# A3000_Backplane.net
KiCad netlist of a schematic drawn in Altium Designer
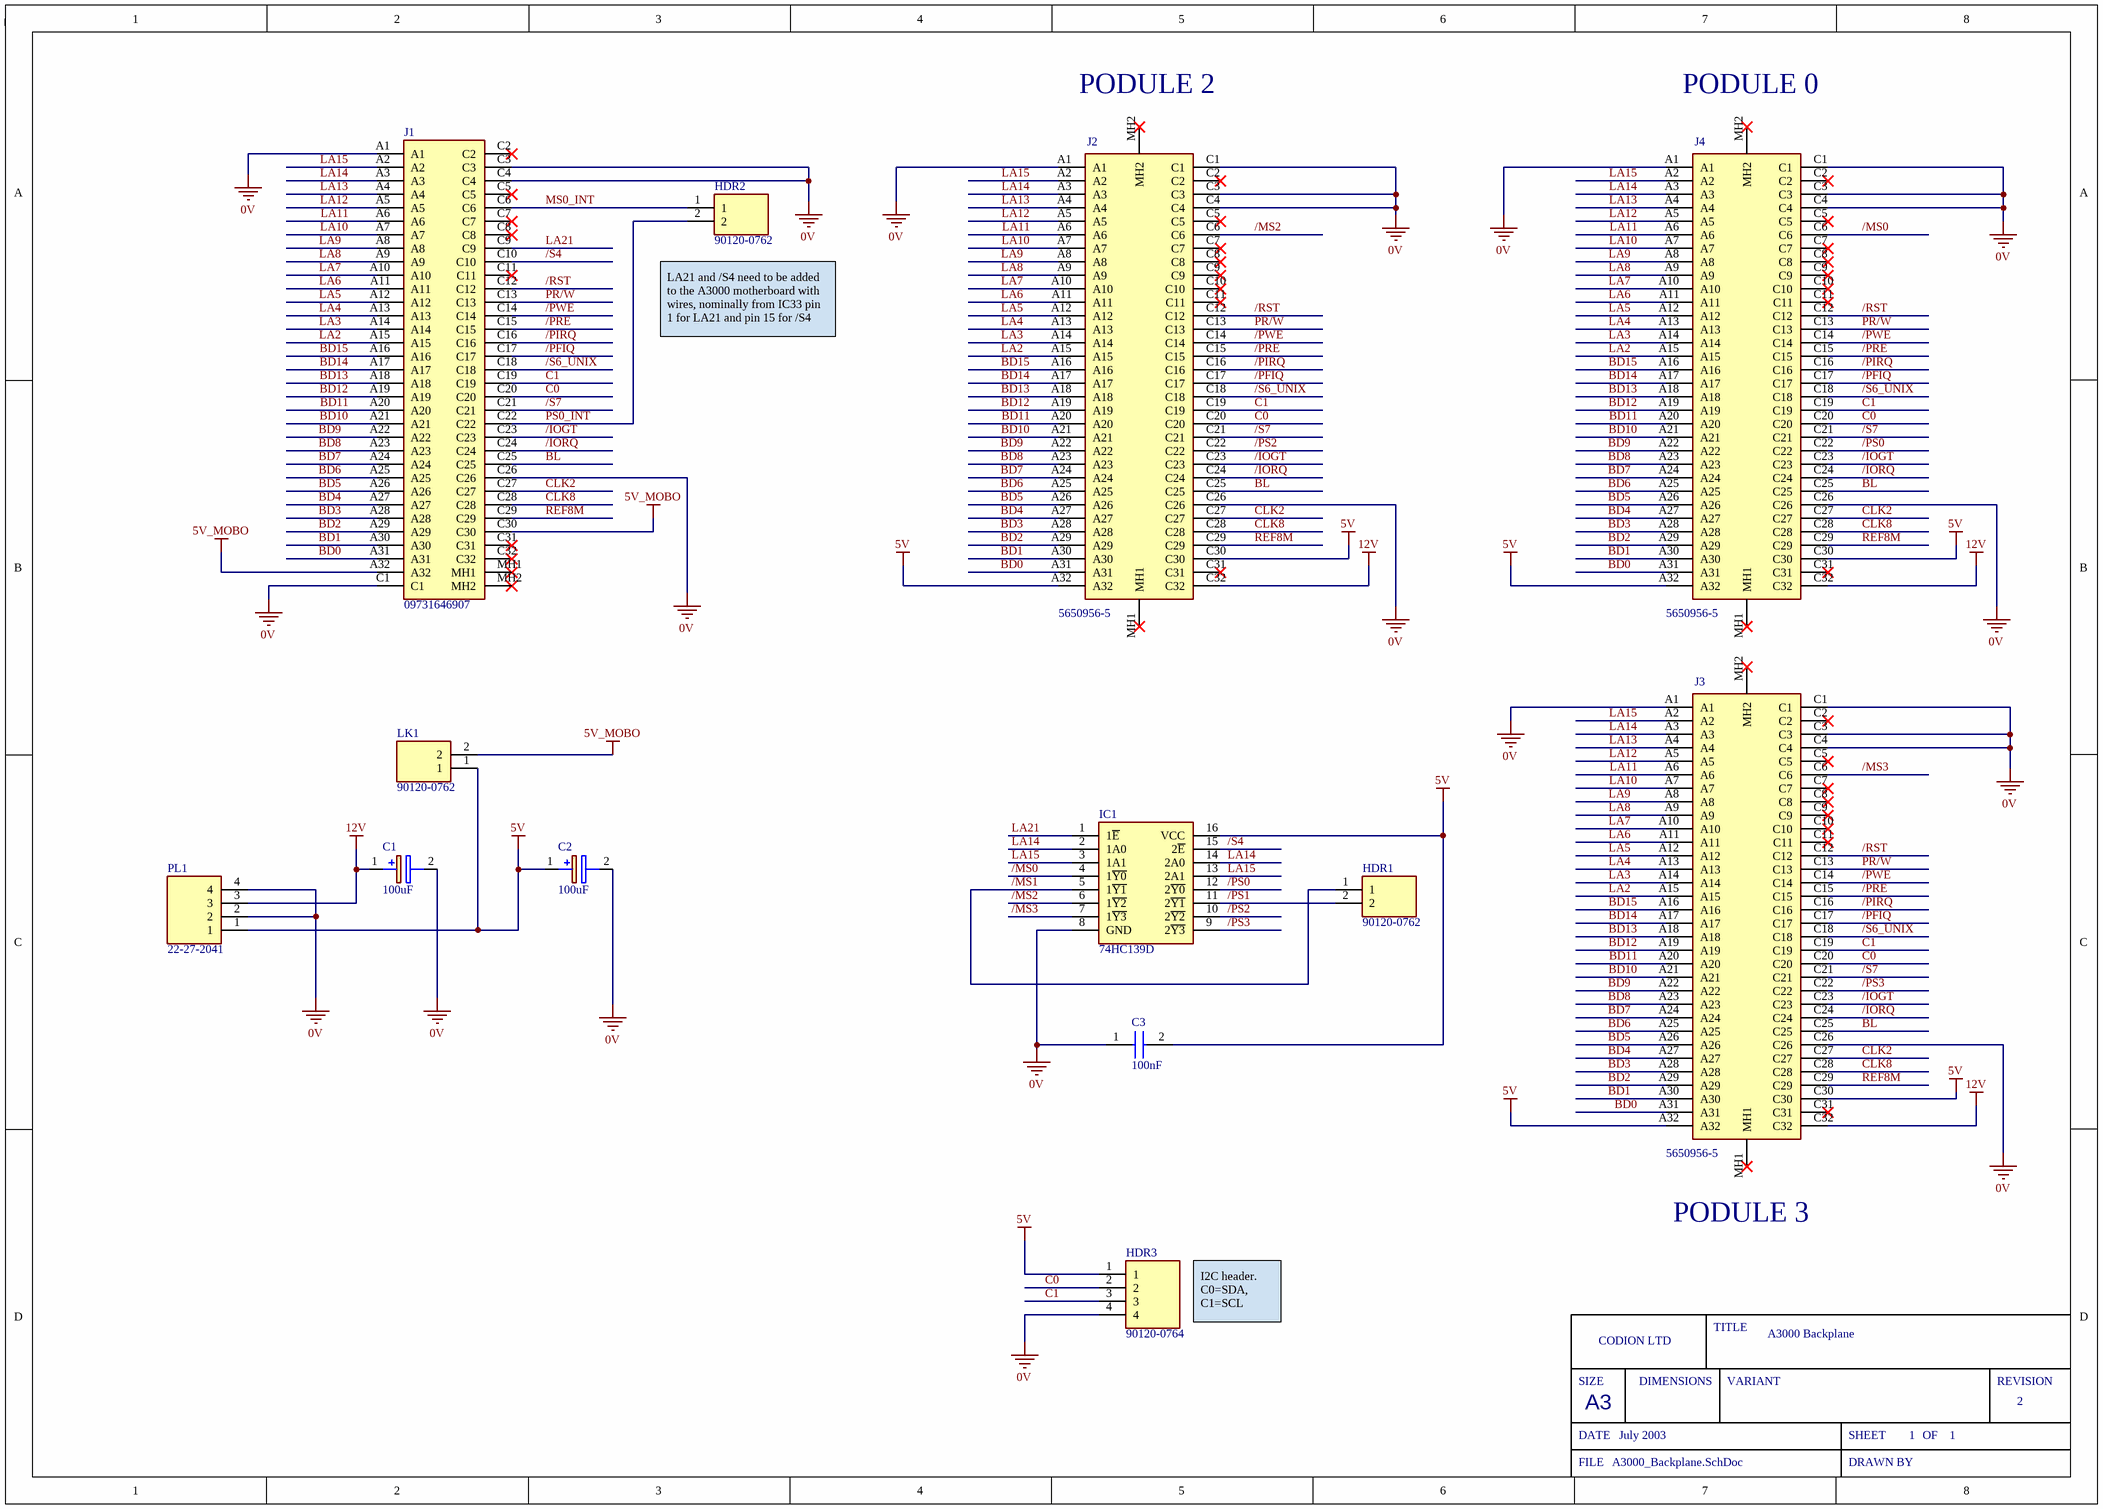
[diagram p0: A3000_Backplane.SchDoc]

(export (version "E")
  (design (tool "Eeschema 10.0.6"))
  (components
    (comp (ref "C1")
      (value "100uF")
      (footprint "SamacSys:EEE0JA331XP")
      (description "Capacitor Polarised")
      (fields
        (field (name "MANUFACTURER_PART_NUMBER") "EEE-TC1C101XP")
        (field (name "MOUSER PART NUMBER") "667-EEE-TC1C101XP")
      )
      (libsource (lib "*") (part "EEE-TC1C101XP"))
    )
    (comp (ref "C2")
      (value "100uF")
      (footprint "SamacSys:EEE0JA331XP")
      (description "Capacitor Polarised")
      (fields
        (field (name "MANUFACTURER_PART_NUMBER") "EEE-TC1C101XP")
        (field (name "MOUSER PART NUMBER") "667-EEE-TC1C101XP")
      )
      (libsource (lib "*") (part "EEE-TC1C101XP"))
    )
    (comp (ref "C3")
      (value "100nF")
      (footprint "SamacSys:CAPC2012X145N")
      (description "Capacitor")
      (fields
        (field (name "MANUFACTURER_PART_NUMBER") "C2012X7R2A104K125AA")
        (field (name "MOUSER PART NUMBER") "810-C2012X7R2A104K")
      )
      (libsource (lib "*") (part "C2012X7R2A104K125AA"))
    )
    (comp (ref "HDR1")
      (value "90120-0762")
      (footprint "SamacSys:HDRV2W35P0X254_1X2_508X249X560P")
      (description "Connector")
      (fields (field (name "MOUSER PART NUMBER") "538-90120-0762"))
      (libsource (lib "") (part "90120-0762_1"))
    )
    (comp (ref "HDR2")
      (value "90120-0762")
      (footprint "SamacSys:HDRV2W35P0X254_1X2_508X249X560P")
      (description "Connector")
      (fields (field (name "MOUSER PART NUMBER") "538-90120-0762"))
      (libsource (lib "") (part "90120-0762_1"))
    )
    (comp (ref "HDR3")
      (value "90120-0764")
      (footprint "SamacSys:HDRV4W90P0X254_1X4_994X249X560P")
      (description "Connector")
      (fields (field (name "MOUSER PART NUMBER") "538-90120-0764"))
      (libsource (lib "*") (part "90120-0764"))
    )
    (comp (ref "IC1")
      (value "74HC139D")
      (footprint "SamacSys:SOIC127P600X175-16N")
      (description "Integrated Circuit")
      (fields (field (name "MOUSER PART NUMBER") "771-74HC139D"))
      (libsource (lib "*") (part "74HC139D"))
    )
    (comp (ref "J1")
      (value "09731646907")
      (footprint "SamacSys:56509455")
      (description "Connector")
      (libsource (lib "*") (part "5650945-5"))
    )
    (comp (ref "J2")
      (value "5650956-5")
      (footprint "SamacSys:56509565")
      (description "Connector")
      (fields (field (name "MOUSER PART NUMBER") "571-5650956-5"))
      (libsource (lib "*") (part "5650956-5"))
    )
    (comp (ref "J3")
      (value "5650956-5")
      (footprint "SamacSys:56509565")
      (description "Connector")
      (fields (field (name "MOUSER PART NUMBER") "571-5650956-5"))
      (libsource (lib "*") (part "5650956-5"))
    )
    (comp (ref "J4")
      (value "5650956-5")
      (footprint "SamacSys:56509565")
      (description "Connector")
      (fields (field (name "MOUSER PART NUMBER") "571-5650956-5"))
      (libsource (lib "*") (part "5650956-5"))
    )
    (comp (ref "LK1")
      (value "90120-0762")
      (footprint "SamacSys:HDRV2W35P0X254_1X2_508X249X560P")
      (description "Connector")
      (fields (field (name "MOUSER PART NUMBER") "538-90120-0762"))
      (libsource (lib "*") (part "90120-0762"))
    )
    (comp (ref "PL1")
      (value "22-27-2041")
      (footprint "SamacSys:SHDR4W64P0X254_1X4_1016X580X1170P")
      (description "Connector")
      (fields (field (name "MOUSER PART NUMBER") "538-22-27-2041"))
      (libsource (lib "*") (part "22-27-2041"))
    )
  )
  (nets
    (net (code "1") (name "/BD0") (class "Default")
      (node (ref "J1") (pin "A31") (pinfunction "A31_A31") (pintype "passive"))
      (node (ref "J2") (pin "A31") (pinfunction "A31_A31") (pintype "passive"))
      (node (ref "J3") (pin "A31") (pinfunction "A31_A31") (pintype "passive"))
      (node (ref "J4") (pin "A31") (pinfunction "A31_A31") (pintype "passive"))
    )
    (net (code "2") (name "/BD1") (class "Default")
      (node (ref "J1") (pin "A30") (pinfunction "A30_A30") (pintype "passive"))
      (node (ref "J2") (pin "A30") (pinfunction "A30_A30") (pintype "passive"))
      (node (ref "J3") (pin "A30") (pinfunction "A30_A30") (pintype "passive"))
      (node (ref "J4") (pin "A30") (pinfunction "A30_A30") (pintype "passive"))
    )
    (net (code "3") (name "/BD2") (class "Default")
      (node (ref "J1") (pin "A29") (pinfunction "A29_A29") (pintype "passive"))
      (node (ref "J2") (pin "A29") (pinfunction "A29_A29") (pintype "passive"))
      (node (ref "J3") (pin "A29") (pinfunction "A29_A29") (pintype "passive"))
      (node (ref "J4") (pin "A29") (pinfunction "A29_A29") (pintype "passive"))
    )
    (net (code "4") (name "/BD3") (class "Default")
      (node (ref "J1") (pin "A28") (pinfunction "A28_A28") (pintype "passive"))
      (node (ref "J2") (pin "A28") (pinfunction "A28_A28") (pintype "passive"))
      (node (ref "J3") (pin "A28") (pinfunction "A28_A28") (pintype "passive"))
      (node (ref "J4") (pin "A28") (pinfunction "A28_A28") (pintype "passive"))
    )
    (net (code "5") (name "/BD4") (class "Default")
      (node (ref "J1") (pin "A27") (pinfunction "A27_A27") (pintype "passive"))
      (node (ref "J2") (pin "A27") (pinfunction "A27_A27") (pintype "passive"))
      (node (ref "J3") (pin "A27") (pinfunction "A27_A27") (pintype "passive"))
      (node (ref "J4") (pin "A27") (pinfunction "A27_A27") (pintype "passive"))
    )
    (net (code "6") (name "/BD5") (class "Default")
      (node (ref "J1") (pin "A26") (pinfunction "A26_A26") (pintype "passive"))
      (node (ref "J2") (pin "A26") (pinfunction "A26_A26") (pintype "passive"))
      (node (ref "J3") (pin "A26") (pinfunction "A26_A26") (pintype "passive"))
      (node (ref "J4") (pin "A26") (pinfunction "A26_A26") (pintype "passive"))
    )
    (net (code "7") (name "/BD6") (class "Default")
      (node (ref "J1") (pin "A25") (pinfunction "A25_A25") (pintype "passive"))
      (node (ref "J2") (pin "A25") (pinfunction "A25_A25") (pintype "passive"))
      (node (ref "J3") (pin "A25") (pinfunction "A25_A25") (pintype "passive"))
      (node (ref "J4") (pin "A25") (pinfunction "A25_A25") (pintype "passive"))
    )
    (net (code "8") (name "/BD7") (class "Default")
      (node (ref "J1") (pin "A24") (pinfunction "A24_A24") (pintype "passive"))
      (node (ref "J2") (pin "A24") (pinfunction "A24_A24") (pintype "passive"))
      (node (ref "J3") (pin "A24") (pinfunction "A24_A24") (pintype "passive"))
      (node (ref "J4") (pin "A24") (pinfunction "A24_A24") (pintype "passive"))
    )
    (net (code "9") (name "/BD8") (class "Default")
      (node (ref "J1") (pin "A23") (pinfunction "A23_A23") (pintype "passive"))
      (node (ref "J2") (pin "A23") (pinfunction "A23_A23") (pintype "passive"))
      (node (ref "J3") (pin "A23") (pinfunction "A23_A23") (pintype "passive"))
      (node (ref "J4") (pin "A23") (pinfunction "A23_A23") (pintype "passive"))
    )
    (net (code "10") (name "/BD9") (class "Default")
      (node (ref "J1") (pin "A22") (pinfunction "A22_A22") (pintype "passive"))
      (node (ref "J2") (pin "A22") (pinfunction "A22_A22") (pintype "passive"))
      (node (ref "J3") (pin "A22") (pinfunction "A22_A22") (pintype "passive"))
      (node (ref "J4") (pin "A22") (pinfunction "A22_A22") (pintype "passive"))
    )
    (net (code "11") (name "/BD10") (class "Default")
      (node (ref "J1") (pin "A21") (pinfunction "A21_A21") (pintype "passive"))
      (node (ref "J2") (pin "A21") (pinfunction "A21_A21") (pintype "passive"))
      (node (ref "J3") (pin "A21") (pinfunction "A21_A21") (pintype "passive"))
      (node (ref "J4") (pin "A21") (pinfunction "A21_A21") (pintype "passive"))
    )
    (net (code "12") (name "/BD11") (class "Default")
      (node (ref "J1") (pin "A20") (pinfunction "A20_A20") (pintype "passive"))
      (node (ref "J2") (pin "A20") (pinfunction "A20_A20") (pintype "passive"))
      (node (ref "J3") (pin "A20") (pinfunction "A20_A20") (pintype "passive"))
      (node (ref "J4") (pin "A20") (pinfunction "A20_A20") (pintype "passive"))
    )
    (net (code "13") (name "/BD12") (class "Default")
      (node (ref "J1") (pin "A19") (pinfunction "A19_A19") (pintype "passive"))
      (node (ref "J2") (pin "A19") (pinfunction "A19_A19") (pintype "passive"))
      (node (ref "J3") (pin "A19") (pinfunction "A19_A19") (pintype "passive"))
      (node (ref "J4") (pin "A19") (pinfunction "A19_A19") (pintype "passive"))
    )
    (net (code "14") (name "/BD13") (class "Default")
      (node (ref "J1") (pin "A18") (pinfunction "A18_A18") (pintype "passive"))
      (node (ref "J2") (pin "A18") (pinfunction "A18_A18") (pintype "passive"))
      (node (ref "J3") (pin "A18") (pinfunction "A18_A18") (pintype "passive"))
      (node (ref "J4") (pin "A18") (pinfunction "A18_A18") (pintype "passive"))
    )
    (net (code "15") (name "/BD14") (class "Default")
      (node (ref "J1") (pin "A17") (pinfunction "A17_A17") (pintype "passive"))
      (node (ref "J2") (pin "A17") (pinfunction "A17_A17") (pintype "passive"))
      (node (ref "J3") (pin "A17") (pinfunction "A17_A17") (pintype "passive"))
      (node (ref "J4") (pin "A17") (pinfunction "A17_A17") (pintype "passive"))
    )
    (net (code "16") (name "/BD15") (class "Default")
      (node (ref "J1") (pin "A16") (pinfunction "A16_A16") (pintype "passive"))
      (node (ref "J2") (pin "A16") (pinfunction "A16_A16") (pintype "passive"))
      (node (ref "J3") (pin "A16") (pinfunction "A16_A16") (pintype "passive"))
      (node (ref "J4") (pin "A16") (pinfunction "A16_A16") (pintype "passive"))
    )
    (net (code "17") (name "/BL") (class "Default")
      (node (ref "J1") (pin "C25") (pinfunction "C25_C25") (pintype "passive"))
      (node (ref "J2") (pin "C25") (pinfunction "C25_C25") (pintype "passive"))
      (node (ref "J3") (pin "C25") (pinfunction "C25_C25") (pintype "passive"))
      (node (ref "J4") (pin "C25") (pinfunction "C25_C25") (pintype "passive"))
    )
    (net (code "18") (name "/C0") (class "Default")
      (node (ref "HDR3") (pin "2") (pinfunction "2_2") (pintype "passive"))
      (node (ref "J1") (pin "C20") (pinfunction "C20_C20") (pintype "passive"))
      (node (ref "J2") (pin "C20") (pinfunction "C20_C20") (pintype "passive"))
      (node (ref "J3") (pin "C20") (pinfunction "C20_C20") (pintype "passive"))
      (node (ref "J4") (pin "C20") (pinfunction "C20_C20") (pintype "passive"))
    )
    (net (code "19") (name "/C1") (class "Default")
      (node (ref "HDR3") (pin "3") (pinfunction "3_3") (pintype "passive"))
      (node (ref "J1") (pin "C19") (pinfunction "C19_C19") (pintype "passive"))
      (node (ref "J2") (pin "C19") (pinfunction "C19_C19") (pintype "passive"))
      (node (ref "J3") (pin "C19") (pinfunction "C19_C19") (pintype "passive"))
      (node (ref "J4") (pin "C19") (pinfunction "C19_C19") (pintype "passive"))
    )
    (net (code "20") (name "/CLK2") (class "Default")
      (node (ref "J1") (pin "C27") (pinfunction "C27_C27") (pintype "passive"))
      (node (ref "J2") (pin "C27") (pinfunction "C27_C27") (pintype "passive"))
      (node (ref "J3") (pin "C27") (pinfunction "C27_C27") (pintype "passive"))
      (node (ref "J4") (pin "C27") (pinfunction "C27_C27") (pintype "passive"))
    )
    (net (code "21") (name "/CLK8") (class "Default")
      (node (ref "J1") (pin "C28") (pinfunction "C28_C28") (pintype "passive"))
      (node (ref "J2") (pin "C28") (pinfunction "C28_C28") (pintype "passive"))
      (node (ref "J3") (pin "C28") (pinfunction "C28_C28") (pintype "passive"))
      (node (ref "J4") (pin "C28") (pinfunction "C28_C28") (pintype "passive"))
    )
    (net (code "22") (name "/LA2") (class "Default")
      (node (ref "J1") (pin "A15") (pinfunction "A15_A15") (pintype "passive"))
      (node (ref "J2") (pin "A15") (pinfunction "A15_A15") (pintype "passive"))
      (node (ref "J3") (pin "A15") (pinfunction "A15_A15") (pintype "passive"))
      (node (ref "J4") (pin "A15") (pinfunction "A15_A15") (pintype "passive"))
    )
    (net (code "23") (name "/LA3") (class "Default")
      (node (ref "J1") (pin "A14") (pinfunction "A14_A14") (pintype "passive"))
      (node (ref "J2") (pin "A14") (pinfunction "A14_A14") (pintype "passive"))
      (node (ref "J3") (pin "A14") (pinfunction "A14_A14") (pintype "passive"))
      (node (ref "J4") (pin "A14") (pinfunction "A14_A14") (pintype "passive"))
    )
    (net (code "24") (name "/LA4") (class "Default")
      (node (ref "J1") (pin "A13") (pinfunction "A13_A13") (pintype "passive"))
      (node (ref "J2") (pin "A13") (pinfunction "A13_A13") (pintype "passive"))
      (node (ref "J3") (pin "A13") (pinfunction "A13_A13") (pintype "passive"))
      (node (ref "J4") (pin "A13") (pinfunction "A13_A13") (pintype "passive"))
    )
    (net (code "25") (name "/LA5") (class "Default")
      (node (ref "J1") (pin "A12") (pinfunction "A12_A12") (pintype "passive"))
      (node (ref "J2") (pin "A12") (pinfunction "A12_A12") (pintype "passive"))
      (node (ref "J3") (pin "A12") (pinfunction "A12_A12") (pintype "passive"))
      (node (ref "J4") (pin "A12") (pinfunction "A12_A12") (pintype "passive"))
    )
    (net (code "26") (name "/LA6") (class "Default")
      (node (ref "J1") (pin "A11") (pinfunction "A11_A11") (pintype "passive"))
      (node (ref "J2") (pin "A11") (pinfunction "A11_A11") (pintype "passive"))
      (node (ref "J3") (pin "A11") (pinfunction "A11_A11") (pintype "passive"))
      (node (ref "J4") (pin "A11") (pinfunction "A11_A11") (pintype "passive"))
    )
    (net (code "27") (name "/LA7") (class "Default")
      (node (ref "J1") (pin "A10") (pinfunction "A10_A10") (pintype "passive"))
      (node (ref "J2") (pin "A10") (pinfunction "A10_A10") (pintype "passive"))
      (node (ref "J3") (pin "A10") (pinfunction "A10_A10") (pintype "passive"))
      (node (ref "J4") (pin "A10") (pinfunction "A10_A10") (pintype "passive"))
    )
    (net (code "28") (name "/LA8") (class "Default")
      (node (ref "J1") (pin "A9") (pinfunction "A9_A9") (pintype "passive"))
      (node (ref "J2") (pin "A9") (pinfunction "A9_A9") (pintype "passive"))
      (node (ref "J3") (pin "A9") (pinfunction "A9_A9") (pintype "passive"))
      (node (ref "J4") (pin "A9") (pinfunction "A9_A9") (pintype "passive"))
    )
    (net (code "29") (name "/LA9") (class "Default")
      (node (ref "J1") (pin "A8") (pinfunction "A8_A8") (pintype "passive"))
      (node (ref "J2") (pin "A8") (pinfunction "A8_A8") (pintype "passive"))
      (node (ref "J3") (pin "A8") (pinfunction "A8_A8") (pintype "passive"))
      (node (ref "J4") (pin "A8") (pinfunction "A8_A8") (pintype "passive"))
    )
    (net (code "30") (name "/LA10") (class "Default")
      (node (ref "J1") (pin "A7") (pinfunction "A7_A7") (pintype "passive"))
      (node (ref "J2") (pin "A7") (pinfunction "A7_A7") (pintype "passive"))
      (node (ref "J3") (pin "A7") (pinfunction "A7_A7") (pintype "passive"))
      (node (ref "J4") (pin "A7") (pinfunction "A7_A7") (pintype "passive"))
    )
    (net (code "31") (name "/LA11") (class "Default")
      (node (ref "J1") (pin "A6") (pinfunction "A6_A6") (pintype "passive"))
      (node (ref "J2") (pin "A6") (pinfunction "A6_A6") (pintype "passive"))
      (node (ref "J3") (pin "A6") (pinfunction "A6_A6") (pintype "passive"))
      (node (ref "J4") (pin "A6") (pinfunction "A6_A6") (pintype "passive"))
    )
    (net (code "32") (name "/LA12") (class "Default")
      (node (ref "J1") (pin "A5") (pinfunction "A5_A5") (pintype "passive"))
      (node (ref "J2") (pin "A5") (pinfunction "A5_A5") (pintype "passive"))
      (node (ref "J3") (pin "A5") (pinfunction "A5_A5") (pintype "passive"))
      (node (ref "J4") (pin "A5") (pinfunction "A5_A5") (pintype "passive"))
    )
    (net (code "33") (name "/LA13") (class "Default")
      (node (ref "J1") (pin "A4") (pinfunction "A4_A4") (pintype "passive"))
      (node (ref "J2") (pin "A4") (pinfunction "A4_A4") (pintype "passive"))
      (node (ref "J3") (pin "A4") (pinfunction "A4_A4") (pintype "passive"))
      (node (ref "J4") (pin "A4") (pinfunction "A4_A4") (pintype "passive"))
    )
    (net (code "34") (name "/LA14") (class "Default")
      (node (ref "IC1") (pin "14") (pinfunction "2A0_14") (pintype "passive"))
      (node (ref "IC1") (pin "2") (pinfunction "1A0_2") (pintype "passive"))
      (node (ref "J1") (pin "A3") (pinfunction "A3_A3") (pintype "passive"))
      (node (ref "J2") (pin "A3") (pinfunction "A3_A3") (pintype "passive"))
      (node (ref "J3") (pin "A3") (pinfunction "A3_A3") (pintype "passive"))
      (node (ref "J4") (pin "A3") (pinfunction "A3_A3") (pintype "passive"))
    )
    (net (code "35") (name "/LA15") (class "Default")
      (node (ref "IC1") (pin "13") (pinfunction "2A1_13") (pintype "passive"))
      (node (ref "IC1") (pin "3") (pinfunction "1A1_3") (pintype "passive"))
      (node (ref "J1") (pin "A2") (pinfunction "A2_A2") (pintype "passive"))
      (node (ref "J2") (pin "A2") (pinfunction "A2_A2") (pintype "passive"))
      (node (ref "J3") (pin "A2") (pinfunction "A2_A2") (pintype "passive"))
      (node (ref "J4") (pin "A2") (pinfunction "A2_A2") (pintype "passive"))
    )
    (net (code "36") (name "/LA21") (class "Default")
      (node (ref "IC1") (pin "1") (pinfunction "1~{E}_1") (pintype "passive"))
      (node (ref "J1") (pin "C9") (pinfunction "C9_C9") (pintype "passive"))
    )
    (net (code "37") (name "/MS0_INT") (class "Default")
      (node (ref "HDR2") (pin "1") (pinfunction "1_1") (pintype "passive"))
      (node (ref "J1") (pin "C6") (pinfunction "C6_C6") (pintype "passive"))
    )
    (net (code "38") (name "/PR{slash}W") (class "Default")
      (node (ref "J1") (pin "C13") (pinfunction "C13_C13") (pintype "passive"))
      (node (ref "J2") (pin "C13") (pinfunction "C13_C13") (pintype "passive"))
      (node (ref "J3") (pin "C13") (pinfunction "C13_C13") (pintype "passive"))
      (node (ref "J4") (pin "C13") (pinfunction "C13_C13") (pintype "passive"))
    )
    (net (code "39") (name "/PS0_INT") (class "Default")
      (node (ref "HDR2") (pin "2") (pinfunction "2_2") (pintype "passive"))
      (node (ref "J1") (pin "C22") (pinfunction "C22_C22") (pintype "passive"))
    )
    (net (code "40") (name "/REF8M") (class "Default")
      (node (ref "J1") (pin "C29") (pinfunction "C29_C29") (pintype "passive"))
      (node (ref "J2") (pin "C29") (pinfunction "C29_C29") (pintype "passive"))
      (node (ref "J3") (pin "C29") (pinfunction "C29_C29") (pintype "passive"))
      (node (ref "J4") (pin "C29") (pinfunction "C29_C29") (pintype "passive"))
    )
    (net (code "41") (name "/{slash}IOGT") (class "Default")
      (node (ref "J1") (pin "C23") (pinfunction "C23_C23") (pintype "passive"))
      (node (ref "J2") (pin "C23") (pinfunction "C23_C23") (pintype "passive"))
      (node (ref "J3") (pin "C23") (pinfunction "C23_C23") (pintype "passive"))
      (node (ref "J4") (pin "C23") (pinfunction "C23_C23") (pintype "passive"))
    )
    (net (code "42") (name "/{slash}IORQ") (class "Default")
      (node (ref "J1") (pin "C24") (pinfunction "C24_C24") (pintype "passive"))
      (node (ref "J2") (pin "C24") (pinfunction "C24_C24") (pintype "passive"))
      (node (ref "J3") (pin "C24") (pinfunction "C24_C24") (pintype "passive"))
      (node (ref "J4") (pin "C24") (pinfunction "C24_C24") (pintype "passive"))
    )
    (net (code "43") (name "/{slash}MS0") (class "Default")
      (node (ref "IC1") (pin "4") (pinfunction "1~{Y0}_4") (pintype "passive"))
      (node (ref "J4") (pin "C6") (pinfunction "C6_C6") (pintype "passive"))
    )
    (net (code "44") (name "/{slash}MS1") (class "Default")
      (node (ref "HDR1") (pin "1") (pinfunction "1_1") (pintype "passive"))
      (node (ref "IC1") (pin "5") (pinfunction "1~{Y1}_5") (pintype "passive"))
    )
    (net (code "45") (name "/{slash}MS2") (class "Default")
      (node (ref "IC1") (pin "6") (pinfunction "1~{Y2}_6") (pintype "passive"))
      (node (ref "J2") (pin "C6") (pinfunction "C6_C6") (pintype "passive"))
    )
    (net (code "46") (name "/{slash}MS3") (class "Default")
      (node (ref "IC1") (pin "7") (pinfunction "1~{Y3}_7") (pintype "passive"))
      (node (ref "J3") (pin "C6") (pinfunction "C6_C6") (pintype "passive"))
    )
    (net (code "47") (name "/{slash}PFIQ") (class "Default")
      (node (ref "J1") (pin "C17") (pinfunction "C17_C17") (pintype "passive"))
      (node (ref "J2") (pin "C17") (pinfunction "C17_C17") (pintype "passive"))
      (node (ref "J3") (pin "C17") (pinfunction "C17_C17") (pintype "passive"))
      (node (ref "J4") (pin "C17") (pinfunction "C17_C17") (pintype "passive"))
    )
    (net (code "48") (name "/{slash}PIRQ") (class "Default")
      (node (ref "J1") (pin "C16") (pinfunction "C16_C16") (pintype "passive"))
      (node (ref "J2") (pin "C16") (pinfunction "C16_C16") (pintype "passive"))
      (node (ref "J3") (pin "C16") (pinfunction "C16_C16") (pintype "passive"))
      (node (ref "J4") (pin "C16") (pinfunction "C16_C16") (pintype "passive"))
    )
    (net (code "49") (name "/{slash}PRE") (class "Default")
      (node (ref "J1") (pin "C15") (pinfunction "C15_C15") (pintype "passive"))
      (node (ref "J2") (pin "C15") (pinfunction "C15_C15") (pintype "passive"))
      (node (ref "J3") (pin "C15") (pinfunction "C15_C15") (pintype "passive"))
      (node (ref "J4") (pin "C15") (pinfunction "C15_C15") (pintype "passive"))
    )
    (net (code "50") (name "/{slash}PS0") (class "Default")
      (node (ref "IC1") (pin "12") (pinfunction "2~{Y0}_12") (pintype "passive"))
      (node (ref "J4") (pin "C22") (pinfunction "C22_C22") (pintype "passive"))
    )
    (net (code "51") (name "/{slash}PS1") (class "Default")
      (node (ref "HDR1") (pin "2") (pinfunction "2_2") (pintype "passive"))
      (node (ref "IC1") (pin "11") (pinfunction "2~{Y1}_11") (pintype "passive"))
    )
    (net (code "52") (name "/{slash}PS2") (class "Default")
      (node (ref "IC1") (pin "10") (pinfunction "2~{Y2}_10") (pintype "passive"))
      (node (ref "J2") (pin "C22") (pinfunction "C22_C22") (pintype "passive"))
    )
    (net (code "53") (name "/{slash}PS3") (class "Default")
      (node (ref "IC1") (pin "9") (pinfunction "2~{Y3}_9") (pintype "passive"))
      (node (ref "J3") (pin "C22") (pinfunction "C22_C22") (pintype "passive"))
    )
    (net (code "54") (name "/{slash}PWE") (class "Default")
      (node (ref "J1") (pin "C14") (pinfunction "C14_C14") (pintype "passive"))
      (node (ref "J2") (pin "C14") (pinfunction "C14_C14") (pintype "passive"))
      (node (ref "J3") (pin "C14") (pinfunction "C14_C14") (pintype "passive"))
      (node (ref "J4") (pin "C14") (pinfunction "C14_C14") (pintype "passive"))
    )
    (net (code "55") (name "/{slash}RST") (class "Default")
      (node (ref "J1") (pin "C12") (pinfunction "C12_C12") (pintype "passive"))
      (node (ref "J2") (pin "C12") (pinfunction "C12_C12") (pintype "passive"))
      (node (ref "J3") (pin "C12") (pinfunction "C12_C12") (pintype "passive"))
      (node (ref "J4") (pin "C12") (pinfunction "C12_C12") (pintype "passive"))
    )
    (net (code "56") (name "/{slash}S4") (class "Default")
      (node (ref "IC1") (pin "15") (pinfunction "2~{E}_15") (pintype "passive"))
      (node (ref "J1") (pin "C10") (pinfunction "C10_C10") (pintype "passive"))
    )
    (net (code "57") (name "/{slash}S6_UNIX") (class "Default")
      (node (ref "J1") (pin "C18") (pinfunction "C18_C18") (pintype "passive"))
      (node (ref "J2") (pin "C18") (pinfunction "C18_C18") (pintype "passive"))
      (node (ref "J3") (pin "C18") (pinfunction "C18_C18") (pintype "passive"))
      (node (ref "J4") (pin "C18") (pinfunction "C18_C18") (pintype "passive"))
    )
    (net (code "58") (name "/{slash}S7") (class "Default")
      (node (ref "J1") (pin "C21") (pinfunction "C21_C21") (pintype "passive"))
      (node (ref "J2") (pin "C21") (pinfunction "C21_C21") (pintype "passive"))
      (node (ref "J3") (pin "C21") (pinfunction "C21_C21") (pintype "passive"))
      (node (ref "J4") (pin "C21") (pinfunction "C21_C21") (pintype "passive"))
    )
    (net (code "59") (name "0V") (class "Default")
      (node (ref "C1") (pin "2") (pinfunction "-_2") (pintype "passive"))
      (node (ref "C2") (pin "2") (pinfunction "-_2") (pintype "passive"))
      (node (ref "C3") (pin "1") (pinfunction "1_1") (pintype "passive"))
      (node (ref "HDR3") (pin "4") (pinfunction "4_4") (pintype "passive"))
      (node (ref "IC1") (pin "8") (pinfunction "GND_8") (pintype "passive"))
      (node (ref "J1") (pin "A1") (pinfunction "A1_A1") (pintype "passive"))
      (node (ref "J1") (pin "C1") (pinfunction "C1_C1") (pintype "passive"))
      (node (ref "J1") (pin "C26") (pinfunction "C26_C26") (pintype "passive"))
      (node (ref "J1") (pin "C3") (pinfunction "C3_C3") (pintype "passive"))
      (node (ref "J1") (pin "C4") (pinfunction "C4_C4") (pintype "passive"))
      (node (ref "J2") (pin "A1") (pinfunction "A1_A1") (pintype "passive"))
      (node (ref "J2") (pin "C1") (pinfunction "C1_C1") (pintype "passive"))
      (node (ref "J2") (pin "C26") (pinfunction "C26_C26") (pintype "passive"))
      (node (ref "J2") (pin "C3") (pinfunction "C3_C3") (pintype "passive"))
      (node (ref "J2") (pin "C4") (pinfunction "C4_C4") (pintype "passive"))
      (node (ref "J3") (pin "A1") (pinfunction "A1_A1") (pintype "passive"))
      (node (ref "J3") (pin "C1") (pinfunction "C1_C1") (pintype "passive"))
      (node (ref "J3") (pin "C26") (pinfunction "C26_C26") (pintype "passive"))
      (node (ref "J3") (pin "C3") (pinfunction "C3_C3") (pintype "passive"))
      (node (ref "J3") (pin "C4") (pinfunction "C4_C4") (pintype "passive"))
      (node (ref "J4") (pin "A1") (pinfunction "A1_A1") (pintype "passive"))
      (node (ref "J4") (pin "C1") (pinfunction "C1_C1") (pintype "passive"))
      (node (ref "J4") (pin "C26") (pinfunction "C26_C26") (pintype "passive"))
      (node (ref "J4") (pin "C3") (pinfunction "C3_C3") (pintype "passive"))
      (node (ref "J4") (pin "C4") (pinfunction "C4_C4") (pintype "passive"))
      (node (ref "PL1") (pin "2") (pinfunction "2_2") (pintype "passive"))
      (node (ref "PL1") (pin "4") (pinfunction "4_4") (pintype "passive"))
    )
    (net (code "60") (name "5V") (class "Default")
      (node (ref "C2") (pin "1") (pinfunction "+_1") (pintype "passive"))
      (node (ref "C3") (pin "2") (pinfunction "2_2") (pintype "passive"))
      (node (ref "HDR3") (pin "1") (pinfunction "1_1") (pintype "passive"))
      (node (ref "IC1") (pin "16") (pinfunction "VCC_16") (pintype "passive"))
      (node (ref "J2") (pin "A32") (pinfunction "A32_A32") (pintype "passive"))
      (node (ref "J2") (pin "C30") (pinfunction "C30_C30") (pintype "passive"))
      (node (ref "J3") (pin "A32") (pinfunction "A32_A32") (pintype "passive"))
      (node (ref "J3") (pin "C30") (pinfunction "C30_C30") (pintype "passive"))
      (node (ref "J4") (pin "A32") (pinfunction "A32_A32") (pintype "passive"))
      (node (ref "J4") (pin "C30") (pinfunction "C30_C30") (pintype "passive"))
      (node (ref "LK1") (pin "1") (pinfunction "1_1") (pintype "passive"))
      (node (ref "PL1") (pin "1") (pinfunction "1_1") (pintype "passive"))
    )
    (net (code "61") (name "5V_MOBO") (class "Default")
      (node (ref "J1") (pin "A32") (pinfunction "A32_A32") (pintype "passive"))
      (node (ref "J1") (pin "C30") (pinfunction "C30_C30") (pintype "passive"))
      (node (ref "LK1") (pin "2") (pinfunction "2_2") (pintype "passive"))
    )
    (net (code "62") (name "12V") (class "Default")
      (node (ref "C1") (pin "1") (pinfunction "+_1") (pintype "passive"))
      (node (ref "J2") (pin "C32") (pinfunction "C32_C32") (pintype "passive"))
      (node (ref "J3") (pin "C32") (pinfunction "C32_C32") (pintype "passive"))
      (node (ref "J4") (pin "C32") (pinfunction "C32_C32") (pintype "passive"))
      (node (ref "PL1") (pin "3") (pinfunction "3_3") (pintype "passive"))
    )
    (net (code "63") (name "unconnected-(J1-PadC2)") (class "Default")
      (node (ref "J1") (pin "C2") (pinfunction "C2_C2") (pintype "passive+no_connect"))
    )
    (net (code "64") (name "unconnected-(J1-PadC5)") (class "Default")
      (node (ref "J1") (pin "C5") (pinfunction "C5_C5") (pintype "passive+no_connect"))
    )
    (net (code "65") (name "unconnected-(J1-PadC7)") (class "Default")
      (node (ref "J1") (pin "C7") (pinfunction "C7_C7") (pintype "passive+no_connect"))
    )
    (net (code "66") (name "unconnected-(J1-PadC8)") (class "Default")
      (node (ref "J1") (pin "C8") (pinfunction "C8_C8") (pintype "passive+no_connect"))
    )
    (net (code "67") (name "unconnected-(J1-PadC11)") (class "Default")
      (node (ref "J1") (pin "C11") (pinfunction "C11_C11") (pintype "passive+no_connect"))
    )
    (net (code "68") (name "unconnected-(J1-PadC31)") (class "Default")
      (node (ref "J1") (pin "C31") (pinfunction "C31_C31") (pintype "passive+no_connect"))
    )
    (net (code "69") (name "unconnected-(J1-PadC32)") (class "Default")
      (node (ref "J1") (pin "C32") (pinfunction "C32_C32") (pintype "passive+no_connect"))
    )
    (net (code "70") (name "unconnected-(J1-PadMH1)") (class "Default")
      (node (ref "J1") (pin "MH1") (pinfunction "MH1_MH1") (pintype "passive+no_connect"))
    )
    (net (code "71") (name "unconnected-(J1-PadMH2)") (class "Default")
      (node (ref "J1") (pin "MH2") (pinfunction "MH2_MH2") (pintype "passive+no_connect"))
    )
    (net (code "72") (name "unconnected-(J2-PadC2)") (class "Default")
      (node (ref "J2") (pin "C2") (pinfunction "C2_C2") (pintype "passive+no_connect"))
    )
    (net (code "73") (name "unconnected-(J2-PadC5)") (class "Default")
      (node (ref "J2") (pin "C5") (pinfunction "C5_C5") (pintype "passive+no_connect"))
    )
    (net (code "74") (name "unconnected-(J2-PadC7)") (class "Default")
      (node (ref "J2") (pin "C7") (pinfunction "C7_C7") (pintype "passive+no_connect"))
    )
    (net (code "75") (name "unconnected-(J2-PadC8)") (class "Default")
      (node (ref "J2") (pin "C8") (pinfunction "C8_C8") (pintype "passive+no_connect"))
    )
    (net (code "76") (name "unconnected-(J2-PadC9)") (class "Default")
      (node (ref "J2") (pin "C9") (pinfunction "C9_C9") (pintype "passive+no_connect"))
    )
    (net (code "77") (name "unconnected-(J2-PadC10)") (class "Default")
      (node (ref "J2") (pin "C10") (pinfunction "C10_C10") (pintype "passive+no_connect"))
    )
    (net (code "78") (name "unconnected-(J2-PadC11)") (class "Default")
      (node (ref "J2") (pin "C11") (pinfunction "C11_C11") (pintype "passive+no_connect"))
    )
    (net (code "79") (name "unconnected-(J2-PadC31)") (class "Default")
      (node (ref "J2") (pin "C31") (pinfunction "C31_C31") (pintype "passive+no_connect"))
    )
    (net (code "80") (name "unconnected-(J2-PadMH1)") (class "Default")
      (node (ref "J2") (pin "MH1") (pinfunction "MH1_MH1") (pintype "passive+no_connect"))
    )
    (net (code "81") (name "unconnected-(J2-PadMH2)") (class "Default")
      (node (ref "J2") (pin "MH2") (pinfunction "MH2_MH2") (pintype "passive+no_connect"))
    )
    (net (code "82") (name "unconnected-(J3-PadC2)") (class "Default")
      (node (ref "J3") (pin "C2") (pinfunction "C2_C2") (pintype "passive+no_connect"))
    )
    (net (code "83") (name "unconnected-(J3-PadC5)") (class "Default")
      (node (ref "J3") (pin "C5") (pinfunction "C5_C5") (pintype "passive+no_connect"))
    )
    (net (code "84") (name "unconnected-(J3-PadC7)") (class "Default")
      (node (ref "J3") (pin "C7") (pinfunction "C7_C7") (pintype "passive+no_connect"))
    )
    (net (code "85") (name "unconnected-(J3-PadC8)") (class "Default")
      (node (ref "J3") (pin "C8") (pinfunction "C8_C8") (pintype "passive+no_connect"))
    )
    (net (code "86") (name "unconnected-(J3-PadC9)") (class "Default")
      (node (ref "J3") (pin "C9") (pinfunction "C9_C9") (pintype "passive+no_connect"))
    )
    (net (code "87") (name "unconnected-(J3-PadC10)") (class "Default")
      (node (ref "J3") (pin "C10") (pinfunction "C10_C10") (pintype "passive+no_connect"))
    )
    (net (code "88") (name "unconnected-(J3-PadC11)") (class "Default")
      (node (ref "J3") (pin "C11") (pinfunction "C11_C11") (pintype "passive+no_connect"))
    )
    (net (code "89") (name "unconnected-(J3-PadC31)") (class "Default")
      (node (ref "J3") (pin "C31") (pinfunction "C31_C31") (pintype "passive+no_connect"))
    )
    (net (code "90") (name "unconnected-(J3-PadMH1)") (class "Default")
      (node (ref "J3") (pin "MH1") (pinfunction "MH1_MH1") (pintype "passive+no_connect"))
    )
    (net (code "91") (name "unconnected-(J3-PadMH2)") (class "Default")
      (node (ref "J3") (pin "MH2") (pinfunction "MH2_MH2") (pintype "passive+no_connect"))
    )
    (net (code "92") (name "unconnected-(J4-PadC2)") (class "Default")
      (node (ref "J4") (pin "C2") (pinfunction "C2_C2") (pintype "passive+no_connect"))
    )
    (net (code "93") (name "unconnected-(J4-PadC5)") (class "Default")
      (node (ref "J4") (pin "C5") (pinfunction "C5_C5") (pintype "passive+no_connect"))
    )
    (net (code "94") (name "unconnected-(J4-PadC7)") (class "Default")
      (node (ref "J4") (pin "C7") (pinfunction "C7_C7") (pintype "passive+no_connect"))
    )
    (net (code "95") (name "unconnected-(J4-PadC8)") (class "Default")
      (node (ref "J4") (pin "C8") (pinfunction "C8_C8") (pintype "passive+no_connect"))
    )
    (net (code "96") (name "unconnected-(J4-PadC9)") (class "Default")
      (node (ref "J4") (pin "C9") (pinfunction "C9_C9") (pintype "passive+no_connect"))
    )
    (net (code "97") (name "unconnected-(J4-PadC10)") (class "Default")
      (node (ref "J4") (pin "C10") (pinfunction "C10_C10") (pintype "passive+no_connect"))
    )
    (net (code "98") (name "unconnected-(J4-PadC11)") (class "Default")
      (node (ref "J4") (pin "C11") (pinfunction "C11_C11") (pintype "passive+no_connect"))
    )
    (net (code "99") (name "unconnected-(J4-PadC31)") (class "Default")
      (node (ref "J4") (pin "C31") (pinfunction "C31_C31") (pintype "passive+no_connect"))
    )
    (net (code "100") (name "unconnected-(J4-PadMH1)") (class "Default")
      (node (ref "J4") (pin "MH1") (pinfunction "MH1_MH1") (pintype "passive+no_connect"))
    )
    (net (code "101") (name "unconnected-(J4-PadMH2)") (class "Default")
      (node (ref "J4") (pin "MH2") (pinfunction "MH2_MH2") (pintype "passive+no_connect"))
    )
  )
)
